# asdr-dual.net
KiCad netlist of a schematic drawn in EAGLE
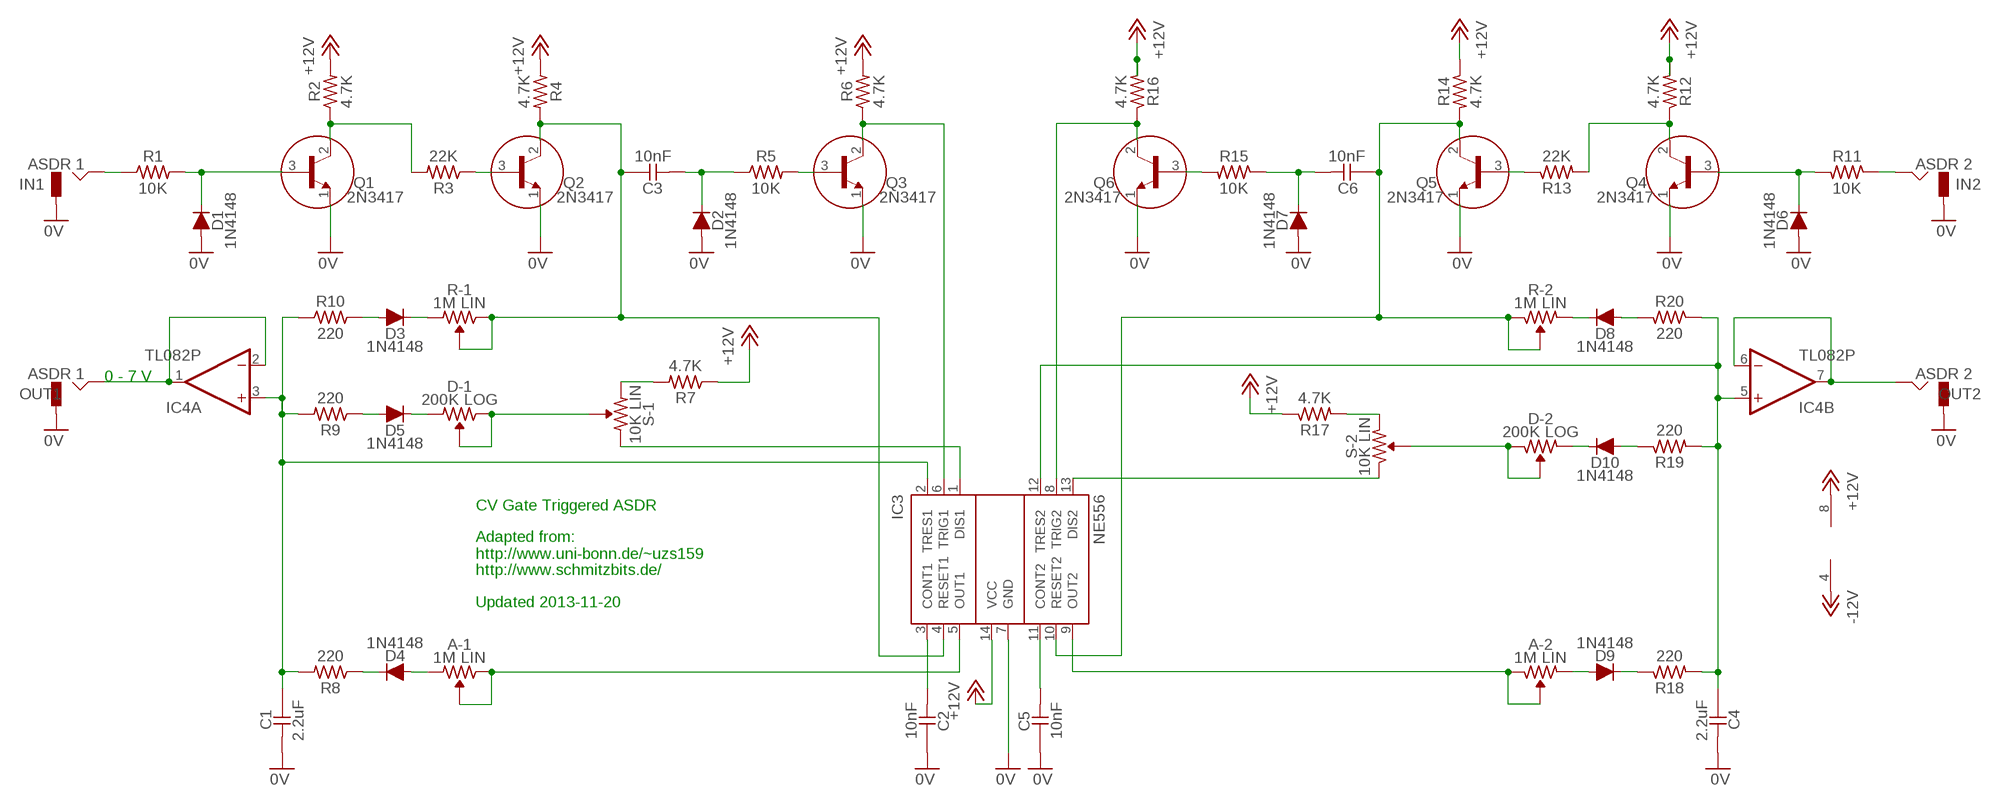
[diagram p0: schematic, sheet 1]

(export (version "E")
  (design (tool "Eeschema 10.0.6"))
  (components
    (comp (ref "A-1")
      (value "1M LIN")
      (footprint "eagle-import:R-VAR")
      (libsource (lib "eagle-import") (part "R-VAR"))
    )
    (comp (ref "A-2")
      (value "1M LIN")
      (footprint "eagle-import:R-VAR")
      (libsource (lib "eagle-import") (part "R-VAR"))
    )
    (comp (ref "C1")
      (value "2.2uF")
      (footprint "eagle-import:C025-024X044")
      (libsource (lib "eagle-import") (part "CC-US025-024X044"))
    )
    (comp (ref "C2")
      (value "10nF")
      (footprint "eagle-import:C025-024X044")
      (libsource (lib "eagle-import") (part "CC-US025-024X044"))
    )
    (comp (ref "C3")
      (value "10nF")
      (footprint "eagle-import:C025-024X044")
      (libsource (lib "eagle-import") (part "CC-US025-024X044"))
    )
    (comp (ref "C4")
      (value "2.2uF")
      (footprint "eagle-import:C025-024X044")
      (libsource (lib "eagle-import") (part "CC-US025-024X044"))
    )
    (comp (ref "C5")
      (value "10nF")
      (footprint "eagle-import:C025-024X044")
      (libsource (lib "eagle-import") (part "CC-US025-024X044"))
    )
    (comp (ref "C6")
      (value "10nF")
      (footprint "eagle-import:C025-024X044")
      (libsource (lib "eagle-import") (part "CC-US025-024X044"))
    )
    (comp (ref "D-1")
      (value "200K LOG")
      (footprint "eagle-import:R-VAR")
      (libsource (lib "eagle-import") (part "R-VAR"))
    )
    (comp (ref "D-2")
      (value "200K LOG")
      (footprint "eagle-import:R-VAR")
      (libsource (lib "eagle-import") (part "R-VAR"))
    )
    (comp (ref "D1")
      (value "1N4148")
      (footprint "eagle-import:DO35-7")
      (libsource (lib "eagle-import") (part "1N4148"))
    )
    (comp (ref "D2")
      (value "1N4148")
      (footprint "eagle-import:DO35-7")
      (libsource (lib "eagle-import") (part "1N4148"))
    )
    (comp (ref "D3")
      (value "1N4148")
      (footprint "eagle-import:DO35-7")
      (libsource (lib "eagle-import") (part "1N4148"))
    )
    (comp (ref "D4")
      (value "1N4148")
      (footprint "eagle-import:DO35-7")
      (libsource (lib "eagle-import") (part "1N4148"))
    )
    (comp (ref "D5")
      (value "1N4148")
      (footprint "eagle-import:DO35-7")
      (libsource (lib "eagle-import") (part "1N4148"))
    )
    (comp (ref "D6")
      (value "1N4148")
      (footprint "eagle-import:DO35-7")
      (libsource (lib "eagle-import") (part "1N4148"))
    )
    (comp (ref "D7")
      (value "1N4148")
      (footprint "eagle-import:DO35-7")
      (libsource (lib "eagle-import") (part "1N4148"))
    )
    (comp (ref "D8")
      (value "1N4148")
      (footprint "eagle-import:DO35-7")
      (libsource (lib "eagle-import") (part "1N4148"))
    )
    (comp (ref "D9")
      (value "1N4148")
      (footprint "eagle-import:DO35-7")
      (libsource (lib "eagle-import") (part "1N4148"))
    )
    (comp (ref "D10")
      (value "1N4148")
      (footprint "eagle-import:DO35-7")
      (libsource (lib "eagle-import") (part "1N4148"))
    )
    (comp (ref "IC3")
      (value "NE556")
      (footprint "eagle-import:DIL14")
      (libsource (lib "eagle-import") (part "NE556"))
    )
    (comp (ref "IC4")
      (value "TL082P")
      (footprint "eagle-import:DIL08")
      (libsource (lib "eagle-import") (part "TL082P"))
    )
    (comp (ref "IN1")
      (value "ASDR 1")
      (footprint "eagle-import:JACK-M")
      (libsource (lib "eagle-import") (part "JACK-M"))
    )
    (comp (ref "IN2")
      (value "ASDR 2")
      (footprint "eagle-import:JACK-M")
      (libsource (lib "eagle-import") (part "JACK-M"))
    )
    (comp (ref "OUT1")
      (value "ASDR 1")
      (footprint "eagle-import:JACK-M")
      (libsource (lib "eagle-import") (part "JACK-M"))
    )
    (comp (ref "OUT2")
      (value "ASDR 2")
      (footprint "eagle-import:JACK-M")
      (libsource (lib "eagle-import") (part "JACK-M"))
    )
    (comp (ref "Q1")
      (value "2N3417")
      (footprint "eagle-import:TO92")
      (libsource (lib "eagle-import") (part "2N3417"))
    )
    (comp (ref "Q2")
      (value "2N3417")
      (footprint "eagle-import:TO92")
      (libsource (lib "eagle-import") (part "2N3417"))
    )
    (comp (ref "Q3")
      (value "2N3417")
      (footprint "eagle-import:TO92")
      (libsource (lib "eagle-import") (part "2N3417"))
    )
    (comp (ref "Q4")
      (value "2N3417")
      (footprint "eagle-import:TO92")
      (libsource (lib "eagle-import") (part "2N3417"))
    )
    (comp (ref "Q5")
      (value "2N3417")
      (footprint "eagle-import:TO92")
      (libsource (lib "eagle-import") (part "2N3417"))
    )
    (comp (ref "Q6")
      (value "2N3417")
      (footprint "eagle-import:TO92")
      (libsource (lib "eagle-import") (part "2N3417"))
    )
    (comp (ref "R-1")
      (value "1M LIN")
      (footprint "eagle-import:R-VAR")
      (libsource (lib "eagle-import") (part "R-VAR"))
    )
    (comp (ref "R-2")
      (value "1M LIN")
      (footprint "eagle-import:R-VAR")
      (libsource (lib "eagle-import") (part "R-VAR"))
    )
    (comp (ref "R1")
      (value "10K")
      (footprint "eagle-import:0309_10")
      (libsource (lib "eagle-import") (part "R0309/10"))
    )
    (comp (ref "R2")
      (value "4.7K")
      (footprint "eagle-import:0309_10")
      (libsource (lib "eagle-import") (part "R0309/10"))
    )
    (comp (ref "R3")
      (value "22K")
      (footprint "eagle-import:0309_10")
      (libsource (lib "eagle-import") (part "R0309/10"))
    )
    (comp (ref "R4")
      (value "4.7K")
      (footprint "eagle-import:0309_10")
      (libsource (lib "eagle-import") (part "R0309/10"))
    )
    (comp (ref "R5")
      (value "10K")
      (footprint "eagle-import:0309_10")
      (libsource (lib "eagle-import") (part "R0309/10"))
    )
    (comp (ref "R6")
      (value "4.7K")
      (footprint "eagle-import:0309_10")
      (libsource (lib "eagle-import") (part "R0309/10"))
    )
    (comp (ref "R7")
      (value "4.7K")
      (footprint "eagle-import:0309_10")
      (libsource (lib "eagle-import") (part "R0309/10"))
    )
    (comp (ref "R8")
      (value "220")
      (footprint "eagle-import:0309_10")
      (libsource (lib "eagle-import") (part "R0309/10"))
    )
    (comp (ref "R9")
      (value "220")
      (footprint "eagle-import:0309_10")
      (libsource (lib "eagle-import") (part "R0309/10"))
    )
    (comp (ref "R10")
      (value "220")
      (footprint "eagle-import:0309_10")
      (libsource (lib "eagle-import") (part "R0309/10"))
    )
    (comp (ref "R11")
      (value "10K")
      (footprint "eagle-import:0309_10")
      (libsource (lib "eagle-import") (part "R0309/10"))
    )
    (comp (ref "R12")
      (value "4.7K")
      (footprint "eagle-import:0309_10")
      (libsource (lib "eagle-import") (part "R0309/10"))
    )
    (comp (ref "R13")
      (value "22K")
      (footprint "eagle-import:0309_10")
      (libsource (lib "eagle-import") (part "R0309/10"))
    )
    (comp (ref "R14")
      (value "4.7K")
      (footprint "eagle-import:0309_10")
      (libsource (lib "eagle-import") (part "R0309/10"))
    )
    (comp (ref "R15")
      (value "10K")
      (footprint "eagle-import:0309_10")
      (libsource (lib "eagle-import") (part "R0309/10"))
    )
    (comp (ref "R16")
      (value "4.7K")
      (footprint "eagle-import:0309_10")
      (libsource (lib "eagle-import") (part "R0309/10"))
    )
    (comp (ref "R17")
      (value "4.7K")
      (footprint "eagle-import:0309_10")
      (libsource (lib "eagle-import") (part "R0309/10"))
    )
    (comp (ref "R18")
      (value "220")
      (footprint "eagle-import:0309_10")
      (libsource (lib "eagle-import") (part "R0309/10"))
    )
    (comp (ref "R19")
      (value "220")
      (footprint "eagle-import:0309_10")
      (libsource (lib "eagle-import") (part "R0309/10"))
    )
    (comp (ref "R20")
      (value "220")
      (footprint "eagle-import:0309_10")
      (libsource (lib "eagle-import") (part "R0309/10"))
    )
    (comp (ref "S-1")
      (value "10K LIN")
      (footprint "eagle-import:R-VAR")
      (libsource (lib "eagle-import") (part "R-VAR"))
    )
    (comp (ref "S-2")
      (value "10K LIN")
      (footprint "eagle-import:R-VAR")
      (libsource (lib "eagle-import") (part "R-VAR"))
    )
  )
  (nets
    (net (code "1") (name "+12V") (class "Default")
      (node (ref "IC3") (pin "14") (pinfunction "VCC_14") (pintype "power_in"))
      (node (ref "IC4") (pin "8") (pinfunction "V+_8") (pintype "power_in"))
      (node (ref "R12") (pin "2") (pinfunction "2_2") (pintype "passive"))
      (node (ref "R14") (pin "1") (pinfunction "1_1") (pintype "passive"))
      (node (ref "R16") (pin "2") (pinfunction "2_2") (pintype "passive"))
      (node (ref "R17") (pin "1") (pinfunction "1_1") (pintype "passive"))
      (node (ref "R2") (pin "2") (pinfunction "2_2") (pintype "passive"))
      (node (ref "R4") (pin "1") (pinfunction "1_1") (pintype "passive"))
      (node (ref "R6") (pin "2") (pinfunction "2_2") (pintype "passive"))
      (node (ref "R7") (pin "1") (pinfunction "1_1") (pintype "passive"))
    )
    (net (code "2") (name "-12V") (class "Default")
      (node (ref "IC4") (pin "4") (pinfunction "V-_4") (pintype "power_in"))
    )
    (net (code "3") (name "0V") (class "Default")
      (node (ref "C1") (pin "2") (pinfunction "2_2") (pintype "passive"))
      (node (ref "C2") (pin "1") (pinfunction "1_1") (pintype "passive"))
      (node (ref "C4") (pin "2") (pinfunction "2_2") (pintype "passive"))
      (node (ref "C5") (pin "1") (pinfunction "1_1") (pintype "passive"))
      (node (ref "D1") (pin "A") (pinfunction "A_A") (pintype "passive"))
      (node (ref "D2") (pin "A") (pinfunction "A_A") (pintype "passive"))
      (node (ref "D6") (pin "A") (pinfunction "A_A") (pintype "passive"))
      (node (ref "D7") (pin "A") (pinfunction "A_A") (pintype "passive"))
      (node (ref "IC3") (pin "7") (pinfunction "GND_7") (pintype "power_in"))
      (node (ref "IN1") (pin "GND") (pinfunction "GND_GND") (pintype "bidirectional"))
      (node (ref "IN2") (pin "GND") (pinfunction "GND_GND") (pintype "bidirectional"))
      (node (ref "OUT1") (pin "GND") (pinfunction "GND_GND") (pintype "bidirectional"))
      (node (ref "OUT2") (pin "GND") (pinfunction "GND_GND") (pintype "bidirectional"))
      (node (ref "Q1") (pin "1") (pinfunction "E_1") (pintype "passive"))
      (node (ref "Q2") (pin "1") (pinfunction "E_1") (pintype "passive"))
      (node (ref "Q3") (pin "1") (pinfunction "E_1") (pintype "passive"))
      (node (ref "Q4") (pin "1") (pinfunction "E_1") (pintype "passive"))
      (node (ref "Q5") (pin "1") (pinfunction "E_1") (pintype "passive"))
      (node (ref "Q6") (pin "1") (pinfunction "E_1") (pintype "passive"))
    )
    (net (code "4") (name "Net-(A-1-1)") (class "Default")
      (node (ref "A-1") (pin "R1") (pinfunction "1_R1") (pintype "passive"))
      (node (ref "A-1") (pin "VAR") (pinfunction "P$1_VAR") (pintype "passive"))
      (node (ref "IC3") (pin "5") (pinfunction "OUT1_5") (pintype "output"))
    )
    (net (code "5") (name "Net-(A-1-2)") (class "Default")
      (node (ref "A-1") (pin "R2") (pinfunction "2_R2") (pintype "passive"))
      (node (ref "D4") (pin "A") (pinfunction "A_A") (pintype "passive"))
    )
    (net (code "6") (name "Net-(A-2-1)") (class "Default")
      (node (ref "A-2") (pin "R1") (pinfunction "1_R1") (pintype "passive"))
      (node (ref "A-2") (pin "VAR") (pinfunction "P$1_VAR") (pintype "passive"))
      (node (ref "IC3") (pin "9") (pinfunction "OUT2_9") (pintype "output"))
    )
    (net (code "7") (name "Net-(A-2-2)") (class "Default")
      (node (ref "A-2") (pin "R2") (pinfunction "2_R2") (pintype "passive"))
      (node (ref "D9") (pin "A") (pinfunction "A_A") (pintype "passive"))
    )
    (net (code "8") (name "Net-(C3-Pad2)") (class "Default")
      (node (ref "C3") (pin "2") (pinfunction "2_2") (pintype "passive"))
      (node (ref "D2") (pin "C") (pinfunction "C_C") (pintype "passive"))
      (node (ref "R5") (pin "1") (pinfunction "1_1") (pintype "passive"))
    )
    (net (code "9") (name "Net-(C6-Pad2)") (class "Default")
      (node (ref "C6") (pin "2") (pinfunction "2_2") (pintype "passive"))
      (node (ref "D7") (pin "C") (pinfunction "C_C") (pintype "passive"))
      (node (ref "R15") (pin "1") (pinfunction "1_1") (pintype "passive"))
    )
    (net (code "10") (name "Net-(D-1-1)") (class "Default")
      (node (ref "D-1") (pin "R1") (pinfunction "1_R1") (pintype "passive"))
      (node (ref "D-1") (pin "VAR") (pinfunction "P$1_VAR") (pintype "passive"))
      (node (ref "S-1") (pin "VAR") (pinfunction "P$1_VAR") (pintype "passive"))
    )
    (net (code "11") (name "Net-(D-1-2)") (class "Default")
      (node (ref "D-1") (pin "R2") (pinfunction "2_R2") (pintype "passive"))
      (node (ref "D5") (pin "C") (pinfunction "C_C") (pintype "passive"))
    )
    (net (code "12") (name "Net-(D-2-1)") (class "Default")
      (node (ref "D-2") (pin "R1") (pinfunction "1_R1") (pintype "passive"))
      (node (ref "D-2") (pin "VAR") (pinfunction "P$1_VAR") (pintype "passive"))
      (node (ref "S-2") (pin "VAR") (pinfunction "P$1_VAR") (pintype "passive"))
    )
    (net (code "13") (name "Net-(D-2-2)") (class "Default")
      (node (ref "D-2") (pin "R2") (pinfunction "2_R2") (pintype "passive"))
      (node (ref "D10") (pin "C") (pinfunction "C_C") (pintype "passive"))
    )
    (net (code "14") (name "Net-(D3-PadA)") (class "Default")
      (node (ref "D3") (pin "A") (pinfunction "A_A") (pintype "passive"))
      (node (ref "R10") (pin "2") (pinfunction "2_2") (pintype "passive"))
    )
    (net (code "15") (name "Net-(D4-PadC)") (class "Default")
      (node (ref "D4") (pin "C") (pinfunction "C_C") (pintype "passive"))
      (node (ref "R8") (pin "1") (pinfunction "1_1") (pintype "passive"))
    )
    (net (code "16") (name "Net-(D5-PadA)") (class "Default")
      (node (ref "D5") (pin "A") (pinfunction "A_A") (pintype "passive"))
      (node (ref "R9") (pin "1") (pinfunction "1_1") (pintype "passive"))
    )
    (net (code "17") (name "Net-(D8-PadA)") (class "Default")
      (node (ref "D8") (pin "A") (pinfunction "A_A") (pintype "passive"))
      (node (ref "R20") (pin "2") (pinfunction "2_2") (pintype "passive"))
    )
    (net (code "18") (name "Net-(D9-PadC)") (class "Default")
      (node (ref "D9") (pin "C") (pinfunction "C_C") (pintype "passive"))
      (node (ref "R18") (pin "1") (pinfunction "1_1") (pintype "passive"))
    )
    (net (code "19") (name "Net-(D10-PadA)") (class "Default")
      (node (ref "D10") (pin "A") (pinfunction "A_A") (pintype "passive"))
      (node (ref "R19") (pin "1") (pinfunction "1_1") (pintype "passive"))
    )
    (net (code "20") (name "Net-(IC3-CONT1)") (class "Default")
      (node (ref "C2") (pin "2") (pinfunction "2_2") (pintype "passive"))
      (node (ref "IC3") (pin "3") (pinfunction "CONT1_3") (pintype "input"))
    )
    (net (code "21") (name "Net-(IC3-CONT2)") (class "Default")
      (node (ref "C5") (pin "2") (pinfunction "2_2") (pintype "passive"))
      (node (ref "IC3") (pin "11") (pinfunction "CONT2_11") (pintype "input"))
    )
    (net (code "22") (name "Net-(IC3-DIS1)") (class "Default")
      (node (ref "IC3") (pin "1") (pinfunction "DIS1_1") (pintype "input"))
      (node (ref "S-1") (pin "R1") (pinfunction "1_R1") (pintype "passive"))
    )
    (net (code "23") (name "Net-(IC3-DIS2)") (class "Default")
      (node (ref "IC3") (pin "13") (pinfunction "DIS2_13") (pintype "input"))
      (node (ref "S-2") (pin "R1") (pinfunction "1_R1") (pintype "passive"))
    )
    (net (code "24") (name "Net-(IC3-RESET1)") (class "Default")
      (node (ref "C3") (pin "1") (pinfunction "1_1") (pintype "passive"))
      (node (ref "IC3") (pin "4") (pinfunction "RESET1_4") (pintype "input"))
      (node (ref "Q2") (pin "2") (pinfunction "C_2") (pintype "passive"))
      (node (ref "R-1") (pin "R1") (pinfunction "1_R1") (pintype "passive"))
      (node (ref "R-1") (pin "VAR") (pinfunction "P$1_VAR") (pintype "passive"))
      (node (ref "R4") (pin "2") (pinfunction "2_2") (pintype "passive"))
    )
    (net (code "25") (name "Net-(IC3-RESET2)") (class "Default")
      (node (ref "C6") (pin "1") (pinfunction "1_1") (pintype "passive"))
      (node (ref "IC3") (pin "10") (pinfunction "RESET2_10") (pintype "input"))
      (node (ref "Q5") (pin "2") (pinfunction "C_2") (pintype "passive"))
      (node (ref "R-2") (pin "R1") (pinfunction "1_R1") (pintype "passive"))
      (node (ref "R-2") (pin "VAR") (pinfunction "P$1_VAR") (pintype "passive"))
      (node (ref "R14") (pin "2") (pinfunction "2_2") (pintype "passive"))
    )
    (net (code "26") (name "Net-(IC3-TRES1)") (class "Default")
      (node (ref "C1") (pin "1") (pinfunction "1_1") (pintype "passive"))
      (node (ref "IC3") (pin "2") (pinfunction "TRES1_2") (pintype "input"))
      (node (ref "IC4") (pin "3") (pinfunction "+IN_3") (pintype "input"))
      (node (ref "R10") (pin "1") (pinfunction "1_1") (pintype "passive"))
      (node (ref "R8") (pin "2") (pinfunction "2_2") (pintype "passive"))
      (node (ref "R9") (pin "2") (pinfunction "2_2") (pintype "passive"))
    )
    (net (code "27") (name "Net-(IC3-TRES2)") (class "Default")
      (node (ref "C4") (pin "1") (pinfunction "1_1") (pintype "passive"))
      (node (ref "IC3") (pin "12") (pinfunction "TRES2_12") (pintype "input"))
      (node (ref "IC4") (pin "5") (pinfunction "+IN_5") (pintype "input"))
      (node (ref "R18") (pin "2") (pinfunction "2_2") (pintype "passive"))
      (node (ref "R19") (pin "2") (pinfunction "2_2") (pintype "passive"))
      (node (ref "R20") (pin "1") (pinfunction "1_1") (pintype "passive"))
    )
    (net (code "28") (name "Net-(IC3-TRIG1)") (class "Default")
      (node (ref "IC3") (pin "6") (pinfunction "TRIG1_6") (pintype "input"))
      (node (ref "Q3") (pin "2") (pinfunction "C_2") (pintype "passive"))
      (node (ref "R6") (pin "1") (pinfunction "1_1") (pintype "passive"))
    )
    (net (code "29") (name "Net-(IC3-TRIG2)") (class "Default")
      (node (ref "IC3") (pin "8") (pinfunction "TRIG2_8") (pintype "input"))
      (node (ref "Q6") (pin "2") (pinfunction "C_2") (pintype "passive"))
      (node (ref "R16") (pin "1") (pinfunction "1_1") (pintype "passive"))
    )
    (net (code "30") (name "Net-(IC4A--IN)") (class "Default")
      (node (ref "IC4") (pin "1") (pinfunction "OUT_1") (pintype "output"))
      (node (ref "IC4") (pin "2") (pinfunction "-IN_2") (pintype "input"))
      (node (ref "OUT1") (pin "HOT") (pinfunction "HOT_HOT") (pintype "bidirectional"))
    )
    (net (code "31") (name "Net-(IC4B--IN)") (class "Default")
      (node (ref "IC4") (pin "6") (pinfunction "-IN_6") (pintype "input"))
      (node (ref "IC4") (pin "7") (pinfunction "OUT_7") (pintype "output"))
      (node (ref "OUT2") (pin "HOT") (pinfunction "HOT_HOT") (pintype "bidirectional"))
    )
    (net (code "32") (name "Net-(IN1-PadHOT)") (class "Default")
      (node (ref "IN1") (pin "HOT") (pinfunction "HOT_HOT") (pintype "bidirectional"))
      (node (ref "R1") (pin "1") (pinfunction "1_1") (pintype "passive"))
    )
    (net (code "33") (name "Net-(IN2-PadHOT)") (class "Default")
      (node (ref "IN2") (pin "HOT") (pinfunction "HOT_HOT") (pintype "bidirectional"))
      (node (ref "R11") (pin "1") (pinfunction "1_1") (pintype "passive"))
    )
    (net (code "34") (name "Net-(Q1-B)") (class "Default")
      (node (ref "D1") (pin "C") (pinfunction "C_C") (pintype "passive"))
      (node (ref "Q1") (pin "3") (pinfunction "B_3") (pintype "passive"))
      (node (ref "R1") (pin "2") (pinfunction "2_2") (pintype "passive"))
    )
    (net (code "35") (name "Net-(Q1-C)") (class "Default")
      (node (ref "Q1") (pin "2") (pinfunction "C_2") (pintype "passive"))
      (node (ref "R2") (pin "1") (pinfunction "1_1") (pintype "passive"))
      (node (ref "R3") (pin "2") (pinfunction "2_2") (pintype "passive"))
    )
    (net (code "36") (name "Net-(Q2-B)") (class "Default")
      (node (ref "Q2") (pin "3") (pinfunction "B_3") (pintype "passive"))
      (node (ref "R3") (pin "1") (pinfunction "1_1") (pintype "passive"))
    )
    (net (code "37") (name "Net-(Q3-B)") (class "Default")
      (node (ref "Q3") (pin "3") (pinfunction "B_3") (pintype "passive"))
      (node (ref "R5") (pin "2") (pinfunction "2_2") (pintype "passive"))
    )
    (net (code "38") (name "Net-(Q4-B)") (class "Default")
      (node (ref "D6") (pin "C") (pinfunction "C_C") (pintype "passive"))
      (node (ref "Q4") (pin "3") (pinfunction "B_3") (pintype "passive"))
      (node (ref "R11") (pin "2") (pinfunction "2_2") (pintype "passive"))
    )
    (net (code "39") (name "Net-(Q4-C)") (class "Default")
      (node (ref "Q4") (pin "2") (pinfunction "C_2") (pintype "passive"))
      (node (ref "R12") (pin "1") (pinfunction "1_1") (pintype "passive"))
      (node (ref "R13") (pin "2") (pinfunction "2_2") (pintype "passive"))
    )
    (net (code "40") (name "Net-(Q5-B)") (class "Default")
      (node (ref "Q5") (pin "3") (pinfunction "B_3") (pintype "passive"))
      (node (ref "R13") (pin "1") (pinfunction "1_1") (pintype "passive"))
    )
    (net (code "41") (name "Net-(Q6-B)") (class "Default")
      (node (ref "Q6") (pin "3") (pinfunction "B_3") (pintype "passive"))
      (node (ref "R15") (pin "2") (pinfunction "2_2") (pintype "passive"))
    )
    (net (code "42") (name "Net-(R-1-2)") (class "Default")
      (node (ref "D3") (pin "C") (pinfunction "C_C") (pintype "passive"))
      (node (ref "R-1") (pin "R2") (pinfunction "2_R2") (pintype "passive"))
    )
    (net (code "43") (name "Net-(R-2-2)") (class "Default")
      (node (ref "D8") (pin "C") (pinfunction "C_C") (pintype "passive"))
      (node (ref "R-2") (pin "R2") (pinfunction "2_R2") (pintype "passive"))
    )
    (net (code "44") (name "Net-(S-1-2)") (class "Default")
      (node (ref "R7") (pin "2") (pinfunction "2_2") (pintype "passive"))
      (node (ref "S-1") (pin "R2") (pinfunction "2_R2") (pintype "passive"))
    )
    (net (code "45") (name "Net-(S-2-2)") (class "Default")
      (node (ref "R17") (pin "2") (pinfunction "2_2") (pintype "passive"))
      (node (ref "S-2") (pin "R2") (pinfunction "2_R2") (pintype "passive"))
    )
  )
)
